# lp_extended.net
KiCad netlist of a schematic drawn in EAGLE
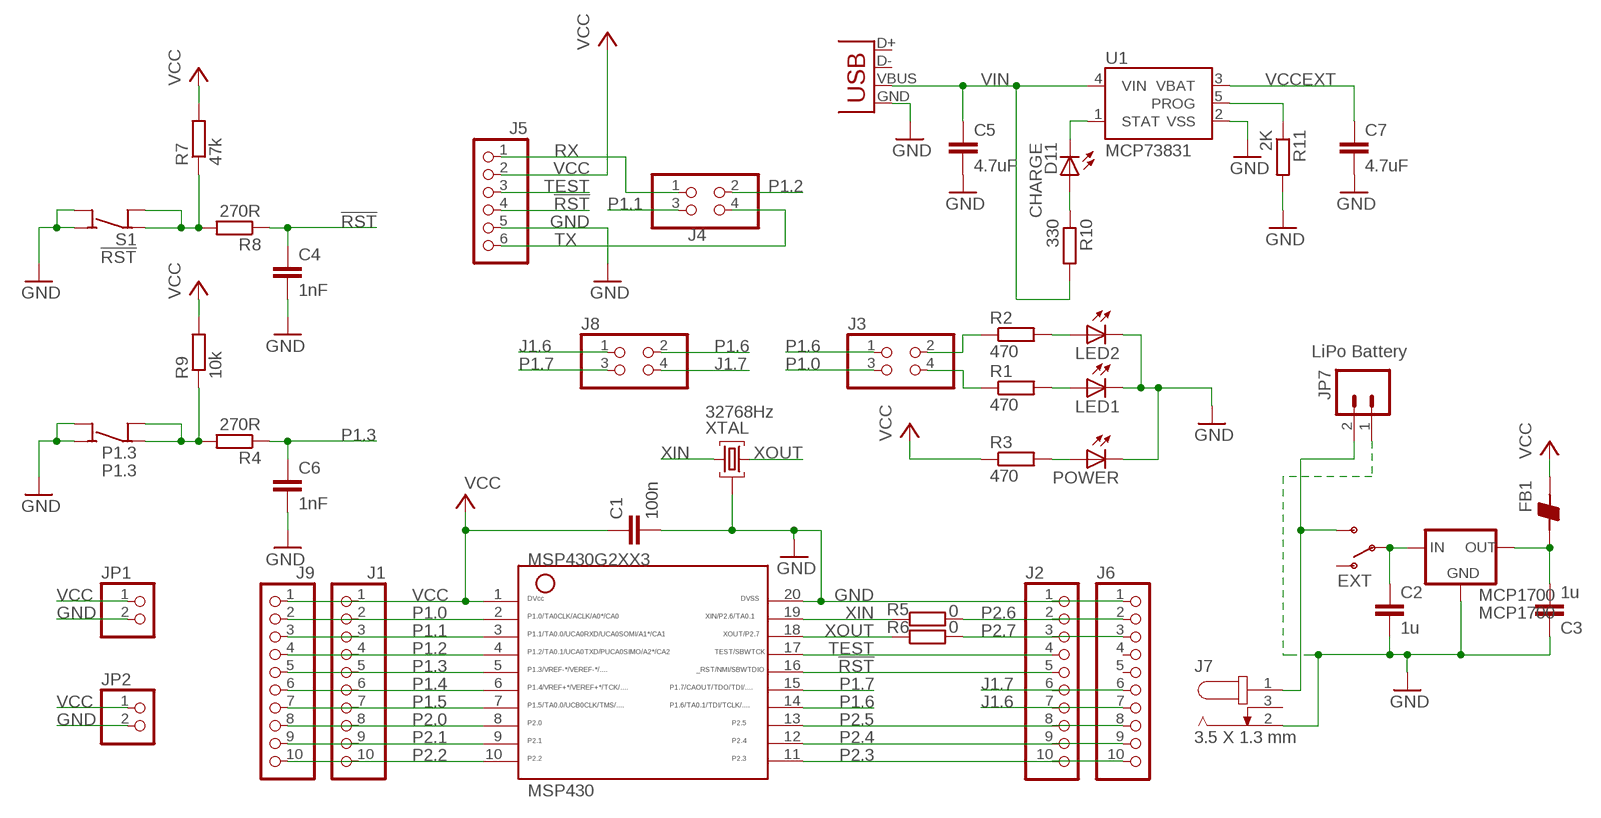
[diagram p0: schematic, sheet 1]

(export (version "E")
  (design (tool "Eeschema 10.0.6"))
  (components
    (comp (ref "C1")
      (value "100n")
      (footprint "eagle-import:C0805")
      (libsource (lib "eagle-import") (part "C-EUC0805"))
    )
    (comp (ref "C2")
      (value "1u")
      (footprint "eagle-import:C0805")
      (libsource (lib "eagle-import") (part "C-EUC0805"))
    )
    (comp (ref "C3")
      (value "1u")
      (footprint "eagle-import:C0805")
      (libsource (lib "eagle-import") (part "C-EUC0805"))
    )
    (comp (ref "C4")
      (value "1nF")
      (footprint "eagle-import:C0805")
      (libsource (lib "eagle-import") (part "resistor_C-EUC0805"))
    )
    (comp (ref "C5")
      (value "4.7uF")
      (footprint "eagle-import:C0805")
      (libsource (lib "eagle-import") (part "resistor_C-EUC0805"))
    )
    (comp (ref "C6")
      (value "1nF")
      (footprint "eagle-import:C0805")
      (libsource (lib "eagle-import") (part "resistor_C-EUC0805"))
    )
    (comp (ref "C7")
      (value "4.7uF")
      (footprint "eagle-import:C0805")
      (libsource (lib "eagle-import") (part "resistor_C-EUC0805"))
    )
    (comp (ref "D11")
      (value "CHARGE")
      (footprint "eagle-import:CHIPLED_1206")
      (libsource (lib "eagle-import") (part "LEDCHIPLED_1206"))
    )
    (comp (ref "FB1")
      (value "BEAD-0805")
      (footprint "eagle-import:0805")
      (libsource (lib "eagle-import") (part "BEAD-0805"))
    )
    (comp (ref "J1")
      (value "PH1X10OCT076")
      (footprint "eagle-import:PH1X10OCT76")
      (libsource (lib "eagle-import") (part "PH1X10OCT076"))
    )
    (comp (ref "J2")
      (value "PH1X10OCT076")
      (footprint "eagle-import:PH1X10OCT76")
      (libsource (lib "eagle-import") (part "PH1X10OCT076"))
    )
    (comp (ref "J3")
      (value "PINHD-2X2")
      (footprint "eagle-import:2X02")
      (libsource (lib "eagle-import") (part "PINHD-2X2"))
    )
    (comp (ref "J4")
      (value "PINHD-2X2")
      (footprint "eagle-import:2X02")
      (libsource (lib "eagle-import") (part "PINHD-2X2"))
    )
    (comp (ref "J5")
      (value "PINHD-1X6")
      (footprint "eagle-import:1X06")
      (libsource (lib "eagle-import") (part "PINHD-1X6"))
    )
    (comp (ref "J6")
      (value "PH1X10OCT076")
      (footprint "eagle-import:PH1X10OCT76")
      (libsource (lib "eagle-import") (part "PH1X10OCT076"))
    )
    (comp (ref "J7")
      (value "3.5 X 1.3 mm")
      (footprint "eagle-import:3.5X1.3MM_DC_JACK")
      (libsource (lib "eagle-import") (part "DC_JACK_3.5X1.3MM"))
    )
    (comp (ref "J8")
      (value "PINHD-2X2")
      (footprint "eagle-import:2X02")
      (libsource (lib "eagle-import") (part "PINHD-2X2"))
    )
    (comp (ref "J9")
      (value "PH1X10OCT076")
      (footprint "eagle-import:PH1X10OCT76")
      (libsource (lib "eagle-import") (part "PH1X10OCT076"))
    )
    (comp (ref "JP1")
      (value "PINHD-1X2")
      (footprint "eagle-import:1X02")
      (libsource (lib "eagle-import") (part "PINHD-1X2"))
    )
    (comp (ref "JP2")
      (value "PINHD-1X2")
      (footprint "eagle-import:1X02")
      (libsource (lib "eagle-import") (part "PINHD-1X2"))
    )
    (comp (ref "JP7")
      (value "LiPo Battery")
      (footprint "eagle-import:JST-2-PTH")
      (libsource (lib "eagle-import") (part "M02JST-PTH-2"))
    )
    (comp (ref "LED1")
      (value "LEDCHIPLED_1206")
      (footprint "eagle-import:CHIPLED_1206")
      (libsource (lib "eagle-import") (part "LEDCHIPLED_1206"))
    )
    (comp (ref "LED2")
      (value "LEDCHIPLED_1206")
      (footprint "eagle-import:CHIPLED_1206")
      (libsource (lib "eagle-import") (part "LEDCHIPLED_1206"))
    )
    (comp (ref "MCP1700")
      (value "MCP1700")
      (footprint "eagle-import:SOT-23")
      (libsource (lib "eagle-import") (part "MCP1700SOT-23"))
    )
    (comp (ref "MSP430")
      (value "MSP430N")
      (footprint "eagle-import:DIP20_HEX")
      (libsource (lib "eagle-import") (part "G2XX3---N20HEX"))
    )
    (comp (ref "ON")
      (value "EXT")
      (footprint "eagle-import:SWITCH-SPDT")
      (libsource (lib "eagle-import") (part "SWITCH-SPSTPTH"))
    )
    (comp (ref "P1.3")
      (value "P1.3")
      (footprint "eagle-import:6MMTACTILE_4PIN")
      (libsource (lib "eagle-import") (part "SPST4"))
    )
    (comp (ref "POWER")
      (value "LEDCHIPLED_1206")
      (footprint "eagle-import:CHIPLED_1206")
      (libsource (lib "eagle-import") (part "LEDCHIPLED_1206"))
    )
    (comp (ref "R1")
      (value "470")
      (footprint "eagle-import:R0805")
      (libsource (lib "eagle-import") (part "resistor_R-EU_R0805"))
    )
    (comp (ref "R2")
      (value "470")
      (footprint "eagle-import:R0805")
      (libsource (lib "eagle-import") (part "resistor_R-EU_R0805"))
    )
    (comp (ref "R3")
      (value "470")
      (footprint "eagle-import:R0805")
      (libsource (lib "eagle-import") (part "resistor_R-EU_R0805"))
    )
    (comp (ref "R4")
      (value "270R")
      (footprint "eagle-import:R0805")
      (libsource (lib "eagle-import") (part "resistor_R-EU_R0805"))
    )
    (comp (ref "R5")
      (value "0")
      (footprint "eagle-import:R0805")
      (libsource (lib "eagle-import") (part "R-EU_R0805"))
    )
    (comp (ref "R6")
      (value "0")
      (footprint "eagle-import:R0805")
      (libsource (lib "eagle-import") (part "R-EU_R0805"))
    )
    (comp (ref "R7")
      (value "47k")
      (footprint "eagle-import:R0805")
      (libsource (lib "eagle-import") (part "resistor_R-EU_R0805"))
    )
    (comp (ref "R8")
      (value "270R")
      (footprint "eagle-import:R0805")
      (libsource (lib "eagle-import") (part "resistor_R-EU_R0805"))
    )
    (comp (ref "R9")
      (value "10k")
      (footprint "eagle-import:R0805")
      (libsource (lib "eagle-import") (part "resistor_R-EU_R0805"))
    )
    (comp (ref "R10")
      (value "330")
      (footprint "eagle-import:R0805")
      (libsource (lib "eagle-import") (part "resistor_R-EU_R0805"))
    )
    (comp (ref "R11")
      (value "2K")
      (footprint "eagle-import:R0805")
      (libsource (lib "eagle-import") (part "resistor_R-EU_R0805"))
    )
    (comp (ref "S1")
      (value "!RST")
      (footprint "eagle-import:6MMTACTILE_4PIN")
      (libsource (lib "eagle-import") (part "SPST4"))
    )
    (comp (ref "U1")
      (value "MCP73831")
      (footprint "eagle-import:SOT23-5")
      (libsource (lib "eagle-import") (part "MCP73831"))
    )
    (comp (ref "X1")
      (value "Mini USB")
      (footprint "eagle-import:USB-MINIB-OLD")
      (libsource (lib "eagle-import") (part "USBOLD"))
    )
    (comp (ref "XTAL")
      (value "32768Hz")
      (footprint "eagle-import:QUARZ5")
      (libsource (lib "eagle-import") (part "QUARZ5"))
    )
  )
  (nets
    (net (code "1") (name "/J1.6") (class "Default")
      (node (ref "J2") (pin "7") (pinfunction "7_7") (pintype "passive"))
      (node (ref "J6") (pin "7") (pinfunction "7_7") (pintype "passive"))
      (node (ref "J8") (pin "1") (pinfunction "1_1") (pintype "passive"))
    )
    (net (code "2") (name "/J1.7") (class "Default")
      (node (ref "J2") (pin "6") (pinfunction "6_6") (pintype "passive"))
      (node (ref "J6") (pin "6") (pinfunction "6_6") (pintype "passive"))
      (node (ref "J8") (pin "4") (pinfunction "4_4") (pintype "passive"))
    )
    (net (code "3") (name "/P1.0") (class "Default")
      (node (ref "J1") (pin "2") (pinfunction "2_2") (pintype "passive"))
      (node (ref "J3") (pin "3") (pinfunction "3_3") (pintype "passive"))
      (node (ref "J9") (pin "2") (pinfunction "2_2") (pintype "passive"))
      (node (ref "MSP430") (pin "2") (pinfunction "2_2") (pintype "bidirectional"))
    )
    (net (code "4") (name "/P1.1") (class "Default")
      (node (ref "J1") (pin "3") (pinfunction "3_3") (pintype "passive"))
      (node (ref "J4") (pin "3") (pinfunction "3_3") (pintype "passive"))
      (node (ref "J9") (pin "3") (pinfunction "3_3") (pintype "passive"))
      (node (ref "MSP430") (pin "3") (pinfunction "3_3") (pintype "bidirectional"))
    )
    (net (code "5") (name "/P1.2") (class "Default")
      (node (ref "J1") (pin "4") (pinfunction "4_4") (pintype "passive"))
      (node (ref "J4") (pin "2") (pinfunction "2_2") (pintype "passive"))
      (node (ref "J9") (pin "4") (pinfunction "4_4") (pintype "passive"))
      (node (ref "MSP430") (pin "4") (pinfunction "4_4") (pintype "bidirectional"))
    )
    (net (code "6") (name "/P1.3") (class "Default")
      (node (ref "C6") (pin "1") (pinfunction "1_1") (pintype "passive"))
      (node (ref "J1") (pin "5") (pinfunction "5_5") (pintype "passive"))
      (node (ref "J9") (pin "5") (pinfunction "5_5") (pintype "passive"))
      (node (ref "MSP430") (pin "5") (pinfunction "5_5") (pintype "bidirectional"))
      (node (ref "R4") (pin "1") (pinfunction "1_1") (pintype "passive"))
    )
    (net (code "7") (name "/P1.4") (class "Default")
      (node (ref "J1") (pin "6") (pinfunction "6_6") (pintype "passive"))
      (node (ref "J9") (pin "6") (pinfunction "6_6") (pintype "passive"))
      (node (ref "MSP430") (pin "6") (pinfunction "6_6") (pintype "bidirectional"))
    )
    (net (code "8") (name "/P1.5") (class "Default")
      (node (ref "J1") (pin "7") (pinfunction "7_7") (pintype "passive"))
      (node (ref "J9") (pin "7") (pinfunction "7_7") (pintype "passive"))
      (node (ref "MSP430") (pin "7") (pinfunction "7_7") (pintype "bidirectional"))
    )
    (net (code "9") (name "/P1.6") (class "Default")
      (node (ref "J3") (pin "1") (pinfunction "1_1") (pintype "passive"))
      (node (ref "J8") (pin "2") (pinfunction "2_2") (pintype "passive"))
      (node (ref "MSP430") (pin "14") (pinfunction "14_14") (pintype "bidirectional"))
    )
    (net (code "10") (name "/P1.7") (class "Default")
      (node (ref "J8") (pin "3") (pinfunction "3_3") (pintype "passive"))
      (node (ref "MSP430") (pin "15") (pinfunction "15_15") (pintype "bidirectional"))
    )
    (net (code "11") (name "/P2.0") (class "Default")
      (node (ref "J1") (pin "8") (pinfunction "8_8") (pintype "passive"))
      (node (ref "J9") (pin "8") (pinfunction "8_8") (pintype "passive"))
      (node (ref "MSP430") (pin "8") (pinfunction "8_8") (pintype "bidirectional"))
    )
    (net (code "12") (name "/P2.1") (class "Default")
      (node (ref "J1") (pin "9") (pinfunction "9_9") (pintype "passive"))
      (node (ref "J9") (pin "9") (pinfunction "9_9") (pintype "passive"))
      (node (ref "MSP430") (pin "9") (pinfunction "9_9") (pintype "bidirectional"))
    )
    (net (code "13") (name "/P2.2") (class "Default")
      (node (ref "J1") (pin "10") (pinfunction "10_10") (pintype "passive"))
      (node (ref "J9") (pin "10") (pinfunction "10_10") (pintype "passive"))
      (node (ref "MSP430") (pin "10") (pinfunction "10_10") (pintype "bidirectional"))
    )
    (net (code "14") (name "/P2.3") (class "Default")
      (node (ref "J2") (pin "10") (pinfunction "10_10") (pintype "passive"))
      (node (ref "J6") (pin "10") (pinfunction "10_10") (pintype "passive"))
      (node (ref "MSP430") (pin "11") (pinfunction "11_11") (pintype "bidirectional"))
    )
    (net (code "15") (name "/P2.4") (class "Default")
      (node (ref "J2") (pin "9") (pinfunction "9_9") (pintype "passive"))
      (node (ref "J6") (pin "9") (pinfunction "9_9") (pintype "passive"))
      (node (ref "MSP430") (pin "12") (pinfunction "12_12") (pintype "bidirectional"))
    )
    (net (code "16") (name "/P2.5") (class "Default")
      (node (ref "J2") (pin "8") (pinfunction "8_8") (pintype "passive"))
      (node (ref "J6") (pin "8") (pinfunction "8_8") (pintype "passive"))
      (node (ref "MSP430") (pin "13") (pinfunction "13_13") (pintype "bidirectional"))
    )
    (net (code "17") (name "/P2.6") (class "Default")
      (node (ref "J2") (pin "2") (pinfunction "2_2") (pintype "passive"))
      (node (ref "J6") (pin "2") (pinfunction "2_2") (pintype "passive"))
      (node (ref "R5") (pin "2") (pinfunction "2_2") (pintype "passive"))
    )
    (net (code "18") (name "/P2.7") (class "Default")
      (node (ref "J2") (pin "3") (pinfunction "3_3") (pintype "passive"))
      (node (ref "J6") (pin "3") (pinfunction "3_3") (pintype "passive"))
      (node (ref "R6") (pin "2") (pinfunction "2_2") (pintype "passive"))
    )
    (net (code "19") (name "/RX") (class "Default")
      (node (ref "J4") (pin "1") (pinfunction "1_1") (pintype "passive"))
      (node (ref "J5") (pin "1") (pinfunction "1_1") (pintype "passive"))
    )
    (net (code "20") (name "/TEST") (class "Default")
      (node (ref "J2") (pin "4") (pinfunction "4_4") (pintype "passive"))
      (node (ref "J5") (pin "3") (pinfunction "3_3") (pintype "passive"))
      (node (ref "MSP430") (pin "17") (pinfunction "17_17") (pintype "bidirectional"))
    )
    (net (code "21") (name "/TX") (class "Default")
      (node (ref "J4") (pin "4") (pinfunction "4_4") (pintype "passive"))
      (node (ref "J5") (pin "6") (pinfunction "6_6") (pintype "passive"))
    )
    (net (code "22") (name "/VCCEXT") (class "Default")
      (node (ref "C7") (pin "1") (pinfunction "1_1") (pintype "passive"))
      (node (ref "J7") (pin "1") (pinfunction "1_1") (pintype "passive"))
      (node (ref "JP7") (pin "2") (pinfunction "2_2") (pintype "passive"))
      (node (ref "ON") (pin "3") (pinfunction "S_3") (pintype "passive"))
      (node (ref "U1") (pin "3") (pinfunction "VBAT_3") (pintype "power_in"))
    )
    (net (code "23") (name "/VIN") (class "Default")
      (node (ref "C5") (pin "1") (pinfunction "1_1") (pintype "passive"))
      (node (ref "R10") (pin "2") (pinfunction "2_2") (pintype "passive"))
      (node (ref "U1") (pin "4") (pinfunction "VIN_4") (pintype "power_in"))
      (node (ref "X1") (pin "VBUS") (pinfunction "VBUS_VBUS") (pintype "bidirectional"))
    )
    (net (code "24") (name "/XIN") (class "Default")
      (node (ref "MSP430") (pin "19") (pinfunction "19_19") (pintype "bidirectional"))
      (node (ref "R5") (pin "1") (pinfunction "1_1") (pintype "passive"))
      (node (ref "XTAL") (pin "2") (pinfunction "2_2") (pintype "passive"))
    )
    (net (code "25") (name "/XOUT") (class "Default")
      (node (ref "MSP430") (pin "18") (pinfunction "18_18") (pintype "bidirectional"))
      (node (ref "R6") (pin "1") (pinfunction "1_1") (pintype "passive"))
      (node (ref "XTAL") (pin "1") (pinfunction "1_1") (pintype "passive"))
    )
    (net (code "26") (name "/~{RST}") (class "Default")
      (node (ref "C4") (pin "1") (pinfunction "1_1") (pintype "passive"))
      (node (ref "J2") (pin "5") (pinfunction "5_5") (pintype "passive"))
      (node (ref "J5") (pin "4") (pinfunction "4_4") (pintype "passive"))
      (node (ref "MSP430") (pin "16") (pinfunction "16_16") (pintype "bidirectional"))
      (node (ref "R8") (pin "1") (pinfunction "1_1") (pintype "passive"))
    )
    (net (code "27") (name "GND") (class "Default")
      (node (ref "C1") (pin "2") (pinfunction "2_2") (pintype "passive"))
      (node (ref "C2") (pin "2") (pinfunction "2_2") (pintype "passive"))
      (node (ref "C3") (pin "1") (pinfunction "1_1") (pintype "passive"))
      (node (ref "C4") (pin "2") (pinfunction "2_2") (pintype "passive"))
      (node (ref "C5") (pin "2") (pinfunction "2_2") (pintype "passive"))
      (node (ref "C6") (pin "2") (pinfunction "2_2") (pintype "passive"))
      (node (ref "C7") (pin "2") (pinfunction "2_2") (pintype "passive"))
      (node (ref "J2") (pin "1") (pinfunction "1_1") (pintype "passive"))
      (node (ref "J5") (pin "5") (pinfunction "5_5") (pintype "passive"))
      (node (ref "J6") (pin "1") (pinfunction "1_1") (pintype "passive"))
      (node (ref "J7") (pin "2") (pinfunction "2_2") (pintype "passive"))
      (node (ref "JP1") (pin "2") (pinfunction "2_2") (pintype "passive"))
      (node (ref "JP2") (pin "2") (pinfunction "2_2") (pintype "passive"))
      (node (ref "JP7") (pin "1") (pinfunction "1_1") (pintype "passive"))
      (node (ref "LED1") (pin "C") (pinfunction "C_C") (pintype "passive"))
      (node (ref "LED2") (pin "C") (pinfunction "C_C") (pintype "passive"))
      (node (ref "MCP1700") (pin "1") (pinfunction "GND_1") (pintype "input"))
      (node (ref "MSP430") (pin "20") (pinfunction "20_20") (pintype "bidirectional"))
      (node (ref "P1.3") (pin "A1") (pinfunction "NO_A1") (pintype "passive"))
      (node (ref "P1.3") (pin "A2") (pinfunction "NO_A2") (pintype "passive"))
      (node (ref "POWER") (pin "C") (pinfunction "C_C") (pintype "passive"))
      (node (ref "R11") (pin "2") (pinfunction "2_2") (pintype "passive"))
      (node (ref "S1") (pin "A1") (pinfunction "NO_A1") (pintype "passive"))
      (node (ref "S1") (pin "A2") (pinfunction "NO_A2") (pintype "passive"))
      (node (ref "U1") (pin "2") (pinfunction "VSS_2") (pintype "power_in"))
      (node (ref "X1") (pin "GND") (pinfunction "GND_GND") (pintype "bidirectional"))
      (node (ref "XTAL") (pin "GND@0") (pinfunction "0_GND@0") (pintype "passive"))
    )
    (net (code "28") (name "Net-(D11-PadA)") (class "Default")
      (node (ref "D11") (pin "A") (pinfunction "A_A") (pintype "passive"))
      (node (ref "R10") (pin "1") (pinfunction "1_1") (pintype "passive"))
    )
    (net (code "29") (name "Net-(FB1-P$1)") (class "Default")
      (node (ref "C3") (pin "2") (pinfunction "2_2") (pintype "passive"))
      (node (ref "FB1") (pin "1") (pinfunction "P$1_1") (pintype "passive"))
      (node (ref "MCP1700") (pin "2") (pinfunction "OUT_2") (pintype "passive"))
    )
    (net (code "30") (name "Net-(J3-Pad2)") (class "Default")
      (node (ref "J3") (pin "2") (pinfunction "2_2") (pintype "passive"))
      (node (ref "R2") (pin "1") (pinfunction "1_1") (pintype "passive"))
    )
    (net (code "31") (name "Net-(J3-Pad4)") (class "Default")
      (node (ref "J3") (pin "4") (pinfunction "4_4") (pintype "passive"))
      (node (ref "R1") (pin "1") (pinfunction "1_1") (pintype "passive"))
    )
    (net (code "32") (name "Net-(LED1-PadA)") (class "Default")
      (node (ref "LED1") (pin "A") (pinfunction "A_A") (pintype "passive"))
      (node (ref "R1") (pin "2") (pinfunction "2_2") (pintype "passive"))
    )
    (net (code "33") (name "Net-(LED2-PadA)") (class "Default")
      (node (ref "LED2") (pin "A") (pinfunction "A_A") (pintype "passive"))
      (node (ref "R2") (pin "2") (pinfunction "2_2") (pintype "passive"))
    )
    (net (code "34") (name "Net-(MCP1700-IN)") (class "Default")
      (node (ref "C2") (pin "1") (pinfunction "1_1") (pintype "passive"))
      (node (ref "MCP1700") (pin "3") (pinfunction "IN_3") (pintype "input"))
      (node (ref "ON") (pin "2") (pinfunction "P_2") (pintype "passive"))
    )
    (net (code "35") (name "Net-(P1.3-COM-PadB1)") (class "Default")
      (node (ref "P1.3") (pin "B1") (pinfunction "COM_B1") (pintype "passive"))
      (node (ref "P1.3") (pin "B2") (pinfunction "COM_B2") (pintype "passive"))
      (node (ref "R4") (pin "2") (pinfunction "2_2") (pintype "passive"))
      (node (ref "R9") (pin "1") (pinfunction "1_1") (pintype "passive"))
    )
    (net (code "36") (name "Net-(POWER-PadA)") (class "Default")
      (node (ref "POWER") (pin "A") (pinfunction "A_A") (pintype "passive"))
      (node (ref "R3") (pin "2") (pinfunction "2_2") (pintype "passive"))
    )
    (net (code "37") (name "Net-(R7-Pad1)") (class "Default")
      (node (ref "R7") (pin "1") (pinfunction "1_1") (pintype "passive"))
      (node (ref "R8") (pin "2") (pinfunction "2_2") (pintype "passive"))
      (node (ref "S1") (pin "B1") (pinfunction "COM_B1") (pintype "passive"))
      (node (ref "S1") (pin "B2") (pinfunction "COM_B2") (pintype "passive"))
    )
    (net (code "38") (name "Net-(U1-PROG)") (class "Default")
      (node (ref "R11") (pin "1") (pinfunction "1_1") (pintype "passive"))
      (node (ref "U1") (pin "5") (pinfunction "PROG_5") (pintype "input"))
    )
    (net (code "39") (name "Net-(U1-STAT)") (class "Default")
      (node (ref "D11") (pin "C") (pinfunction "C_C") (pintype "passive"))
      (node (ref "U1") (pin "1") (pinfunction "STAT_1") (pintype "output"))
    )
    (net (code "40") (name "VCC") (class "Default")
      (node (ref "C1") (pin "1") (pinfunction "1_1") (pintype "passive"))
      (node (ref "FB1") (pin "2") (pinfunction "P$2_2") (pintype "passive"))
      (node (ref "J1") (pin "1") (pinfunction "1_1") (pintype "passive"))
      (node (ref "J5") (pin "2") (pinfunction "2_2") (pintype "passive"))
      (node (ref "J9") (pin "1") (pinfunction "1_1") (pintype "passive"))
      (node (ref "JP1") (pin "1") (pinfunction "1_1") (pintype "passive"))
      (node (ref "JP2") (pin "1") (pinfunction "1_1") (pintype "passive"))
      (node (ref "MSP430") (pin "1") (pinfunction "1_1") (pintype "bidirectional"))
      (node (ref "R3") (pin "1") (pinfunction "1_1") (pintype "passive"))
      (node (ref "R7") (pin "2") (pinfunction "2_2") (pintype "passive"))
      (node (ref "R9") (pin "2") (pinfunction "2_2") (pintype "passive"))
    )
    (net (code "41") (name "unconnected-(J6-Pad4)") (class "Default")
      (node (ref "J6") (pin "4") (pinfunction "4_4") (pintype "passive"))
    )
    (net (code "42") (name "unconnected-(J6-Pad5)") (class "Default")
      (node (ref "J6") (pin "5") (pinfunction "5_5") (pintype "passive"))
    )
    (net (code "43") (name "unconnected-(J7-Pad3)") (class "Default")
      (node (ref "J7") (pin "3") (pinfunction "3_3") (pintype "passive"))
    )
    (net (code "44") (name "unconnected-(ON-O-Pad1)") (class "Default")
      (node (ref "ON") (pin "1") (pinfunction "O_1") (pintype "passive"))
    )
    (net (code "45") (name "unconnected-(X1-PadD+)") (class "Default")
      (node (ref "X1") (pin "D+") (pinfunction "D+_D+") (pintype "bidirectional"))
    )
    (net (code "46") (name "unconnected-(X1-PadD-)") (class "Default")
      (node (ref "X1") (pin "D-") (pinfunction "D-_D-") (pintype "bidirectional"))
    )
  )
)
